# CONTROL-PANEL.net
KiCad netlist of a schematic drawn in Altium Designer
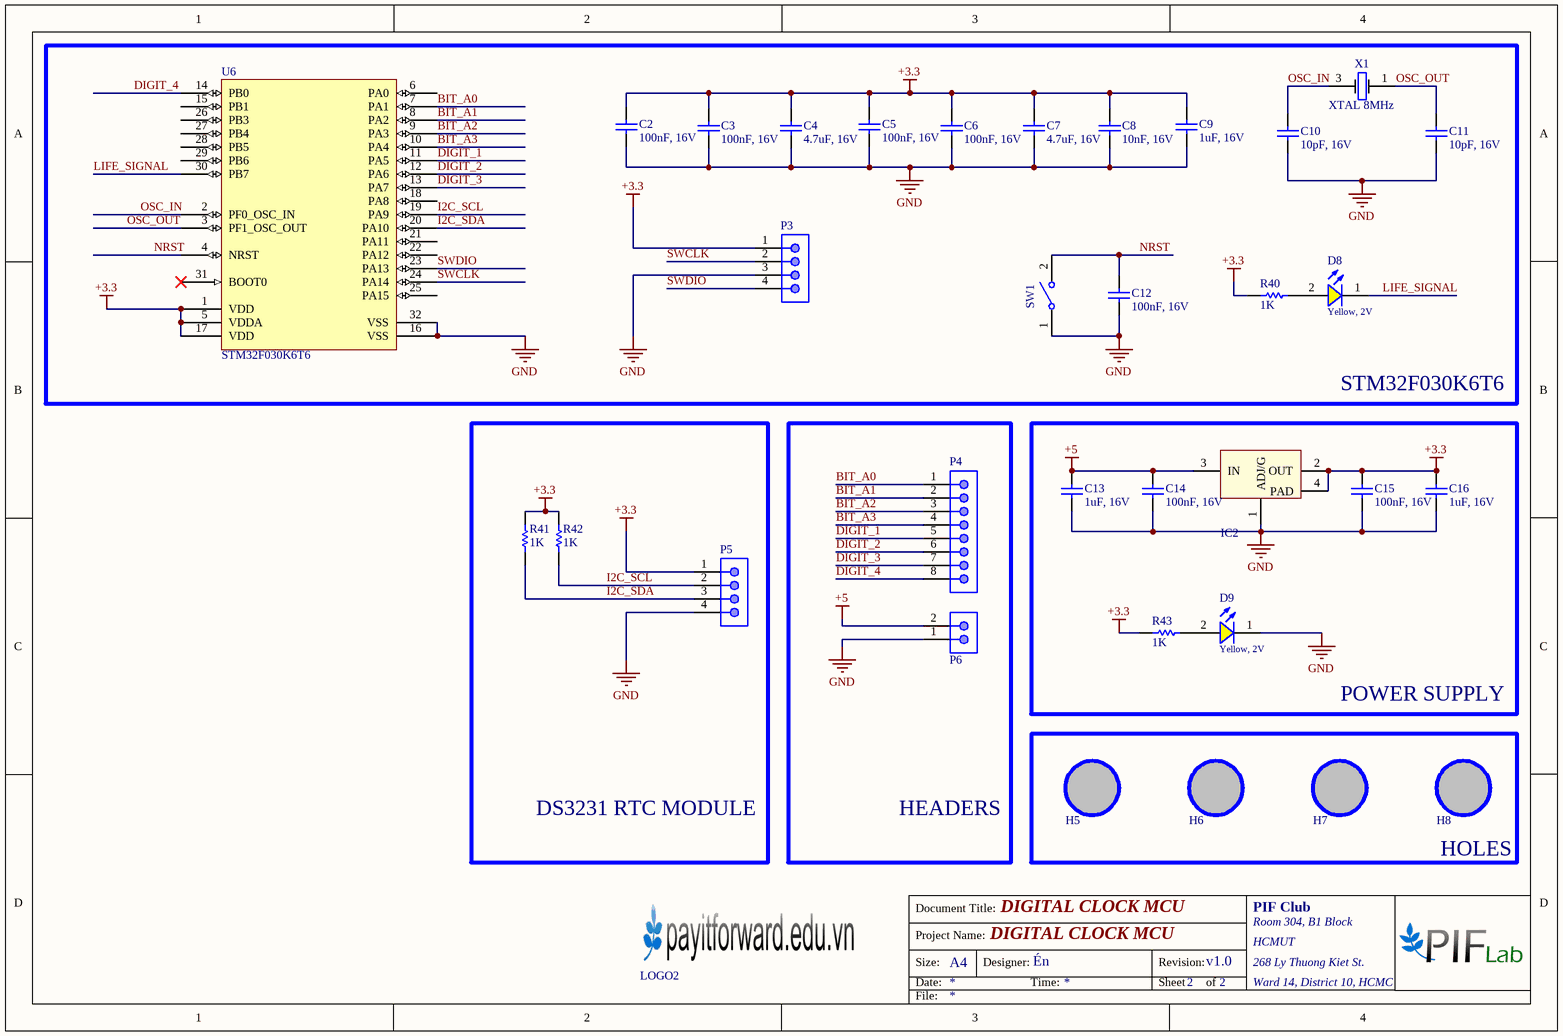
[diagram p0: CONTROL-PANEL.SchDoc]

(export (version "E")
  (design (tool "Eeschema 10.0.6"))
  (components
    (comp (ref "C2")
      (value "100nF, 16V")
      (footprint "CAP-SM-0603")
      (description "Capacitor")
      (fields (field (name "Comment") "Cap Non-Pol SMD"))
      (libsource (lib "PIF_Library") (part "Cap Non-Pol SMD"))
    )
    (comp (ref "C3")
      (value "100nF, 16V")
      (footprint "CAP-SM-0603")
      (description "Capacitor")
      (fields (field (name "Comment") "Cap Non-Pol SMD"))
      (libsource (lib "PIF_Library") (part "Cap Non-Pol SMD"))
    )
    (comp (ref "C4")
      (value "4.7uF, 16V")
      (footprint "CAP-SM-0603")
      (description "Capacitor")
      (fields (field (name "Comment") "Cap Non-Pol SMD"))
      (libsource (lib "PIF_Library") (part "Cap Non-Pol SMD"))
    )
    (comp (ref "C5")
      (value "100nF, 16V")
      (footprint "CAP-SM-0603")
      (description "Capacitor")
      (fields (field (name "Comment") "Cap Non-Pol SMD"))
      (libsource (lib "PIF_Library") (part "Cap Non-Pol SMD"))
    )
    (comp (ref "C6")
      (value "100nF, 16V")
      (footprint "CAP-SM-0603")
      (description "Capacitor")
      (fields (field (name "Comment") "Cap Non-Pol SMD"))
      (libsource (lib "PIF_Library") (part "Cap Non-Pol SMD"))
    )
    (comp (ref "C7")
      (value "4.7uF, 16V")
      (footprint "CAP-SM-0603")
      (description "Capacitor")
      (fields (field (name "Comment") "Cap Non-Pol SMD"))
      (libsource (lib "PIF_Library") (part "Cap Non-Pol SMD"))
    )
    (comp (ref "C8")
      (value "10nF, 16V")
      (footprint "CAP-SM-0603")
      (description "Capacitor")
      (fields (field (name "Comment") "Cap Non-Pol SMD"))
      (libsource (lib "PIF_Library") (part "Cap Non-Pol SMD"))
    )
    (comp (ref "C9")
      (value "1uF, 16V")
      (footprint "CAP-SM-0603")
      (description "Capacitor")
      (fields (field (name "Comment") "Cap Non-Pol SMD"))
      (libsource (lib "PIF_Library") (part "Cap Non-Pol SMD"))
    )
    (comp (ref "C10")
      (value "10pF, 16V")
      (footprint "CAP-SM-0603")
      (description "Capacitor")
      (fields (field (name "Comment") "Cap Non-Pol SMD"))
      (libsource (lib "PIF_Library") (part "Cap Non-Pol SMD"))
    )
    (comp (ref "C11")
      (value "10pF, 16V")
      (footprint "CAP-SM-0603")
      (description "Capacitor")
      (fields (field (name "Comment") "Cap Non-Pol SMD"))
      (libsource (lib "PIF_Library") (part "Cap Non-Pol SMD"))
    )
    (comp (ref "C12")
      (value "100nF, 16V")
      (footprint "CAP-SM-0603")
      (description "Capacitor")
      (fields (field (name "Comment") "Cap Non-Pol SMD"))
      (libsource (lib "PIF_Library") (part "Cap Non-Pol SMD"))
    )
    (comp (ref "C13")
      (value "1uF, 16V")
      (footprint "CAP-SM-0603")
      (description "Capacitor")
      (fields (field (name "Comment") "Cap Non-Pol SMD"))
      (libsource (lib "PIF_Library") (part "Cap Non-Pol SMD"))
    )
    (comp (ref "C14")
      (value "100nF, 16V")
      (footprint "CAP-SM-0603")
      (description "Capacitor")
      (fields (field (name "Comment") "Cap Non-Pol SMD"))
      (libsource (lib "PIF_Library") (part "Cap Non-Pol SMD"))
    )
    (comp (ref "C15")
      (value "100nF, 16V")
      (footprint "CAP-SM-0603")
      (description "Capacitor")
      (fields (field (name "Comment") "Cap Non-Pol SMD"))
      (libsource (lib "PIF_Library") (part "Cap Non-Pol SMD"))
    )
    (comp (ref "C16")
      (value "1uF, 16V")
      (footprint "CAP-SM-0603")
      (description "Capacitor")
      (fields (field (name "Comment") "Cap Non-Pol SMD"))
      (libsource (lib "PIF_Library") (part "Cap Non-Pol SMD"))
    )
    (comp (ref "D8")
      (value "Yellow, 2V")
      (footprint "WL-SMCW_0603_H=0.7mm")
      (description "WL-SMCW SMT Mono-color Chip LED Waterclear, size 0603, Yellow, 2V, 140deg")
      (fields (field (name "PART NUMBER") "150060YS75000") (field (name "PUBLISHER") "Wurth Elektronik"))
      (libsource (lib "Altium_WL-SMCW (rev20a)") (part "150060YS75000"))
    )
    (comp (ref "D9")
      (value "Yellow, 2V")
      (footprint "WL-SMCW_0603_H=0.7mm")
      (description "WL-SMCW SMT Mono-color Chip LED Waterclear, size 0603, Yellow, 2V, 140deg")
      (fields (field (name "PART NUMBER") "150060YS75000") (field (name "PUBLISHER") "Wurth Elektronik"))
      (libsource (lib "Altium_WL-SMCW (rev20a)") (part "150060YS75000"))
    )
    (comp (ref "H5")
      (value "Hole")
      (footprint "LO KHOAN 3MM")
      (description "Hole 3mm")
      (libsource (lib "PIF_Library") (part "Hole"))
    )
    (comp (ref "H6")
      (value "Hole")
      (footprint "LO KHOAN 3MM")
      (description "Hole 3mm")
      (libsource (lib "PIF_Library") (part "Hole"))
    )
    (comp (ref "H7")
      (value "Hole")
      (footprint "LO KHOAN 3MM")
      (description "Hole 3mm")
      (libsource (lib "PIF_Library") (part "Hole"))
    )
    (comp (ref "H8")
      (value "Hole")
      (footprint "LO KHOAN 3MM")
      (description "Hole 3mm")
      (libsource (lib "PIF_Library") (part "Hole"))
    )
    (comp (ref "IC2")
      (value "LM1117")
      (footprint "SOT223-4N")
      (description "Available in 1.8V, 2.5V, 2.85V, 3.3V, 5V, and  Adjustable Versions")
      (libsource (lib "PIF_Library") (part "LM1117"))
    )
    (comp (ref "LOGO2")
      (value "LOGO PIF")
      (footprint "PIF LOGO SMALL SSTOP")
      (libsource (lib "PIF_Library") (part "LOGO PIF"))
    )
    (comp (ref "P3")
      (value "61900411121")
      (footprint "61900411121")
      (description "WR-WTB THT Male Vertical Locking Header, pitch 2.54mm, 4p")
      (fields (field (name "PUBLISHER") "Wurth Elektronik"))
      (libsource (lib "653008114822_Altium_WR-WTB_rev20a") (part "61900411121"))
    )
    (comp (ref "P4")
      (value "62000811622")
      (footprint "62000811622")
      (description "WR-WTB Male Vertical Shrouded Header, pitch 2mm, 8p")
      (fields (field (name "PUBLISHER") "Wurth Elektronik"))
      (libsource (lib "653008114822_Altium_WR-WTB_rev20a") (part "62000811622"))
    )
    (comp (ref "P5")
      (value "62000411622")
      (footprint "62000411622")
      (description "WR-WTB Male Vertical Shrouded Header, pitch 2mm, 4p")
      (fields (field (name "PUBLISHER") "Wurth Elektronik"))
      (libsource (lib "653008114822_Altium_WR-WTB_rev20a") (part "62000411622"))
    )
    (comp (ref "P6")
      (value "62000211622")
      (footprint "62000211622")
      (description "WR-WTB Male Vertical Shrouded Header, pitch 2mm, 2p")
      (fields (field (name "PUBLISHER") "Wurth Elektronik"))
      (libsource (lib "653008114822_Altium_WR-WTB_rev20a") (part "62000211622"))
    )
    (comp (ref "R40")
      (value "1K")
      (footprint "RES-SM-0603")
      (description "Resistor")
      (fields (field (name "Comment") "RESISTOR SMD"))
      (libsource (lib "PIF_Library") (part "RESISTOR SMD"))
    )
    (comp (ref "R41")
      (value "1K")
      (footprint "RES-SM-0603")
      (description "Resistor")
      (fields (field (name "Comment") "RESISTOR SMD"))
      (libsource (lib "PIF_Library") (part "RESISTOR SMD"))
    )
    (comp (ref "R42")
      (value "1K")
      (footprint "RES-SM-0603")
      (description "Resistor")
      (fields (field (name "Comment") "RESISTOR SMD"))
      (libsource (lib "PIF_Library") (part "RESISTOR SMD"))
    )
    (comp (ref "R43")
      (value "1K")
      (footprint "RES-SM-0603")
      (description "Resistor")
      (fields (field (name "Comment") "RESISTOR SMD"))
      (libsource (lib "PIF_Library") (part "RESISTOR SMD"))
    )
    (comp (ref "SW1")
      (value "434111025826")
      (footprint "WS-TASV_L6W3.8H2.5_4341x10258x6")
      (description "WS-TASV SMT Tact Switch, 12VDC, 50mA, 260g, height 2.5mm")
      (fields (field (name "MANUFACTURER") "Wurth Elektronik"))
      (libsource (lib "Altium_WS-TASV (rev22a)") (part "434111025826"))
    )
    (comp (ref "U6")
      (value "STM32F030K6T6")
      (footprint "STM32F030K6T6")
      (description "ARM Cortex M0 Microcontroller IC 32-Bit 48MHz 32KB FLASH, 32-LQFP")
      (fields (field (name "MFR") "STMicroelectronics"))
      (libsource (lib "Giang's Libs") (part "STM32F030K6T6"))
    )
    (comp (ref "X1") (value "XTAL 8MHz") (footprint "XTAL 3225") (libsource (lib "MiclsLib") (part "XTAL")))
  )
  (nets
    (net (code "1") (name "+3.3") (class "Default")
      (node (ref "C15") (pin "2") (pinfunction "2_2") (pintype "passive"))
      (node (ref "C16") (pin "2") (pinfunction "2_2") (pintype "passive"))
      (node (ref "C2") (pin "2") (pinfunction "2_2") (pintype "passive"))
      (node (ref "C3") (pin "2") (pinfunction "2_2") (pintype "passive"))
      (node (ref "C4") (pin "2") (pinfunction "2_2") (pintype "passive"))
      (node (ref "C5") (pin "2") (pinfunction "2_2") (pintype "passive"))
      (node (ref "C6") (pin "2") (pinfunction "2_2") (pintype "passive"))
      (node (ref "C7") (pin "2") (pinfunction "2_2") (pintype "passive"))
      (node (ref "C8") (pin "2") (pinfunction "2_2") (pintype "passive"))
      (node (ref "C9") (pin "2") (pinfunction "2_2") (pintype "passive"))
      (node (ref "IC2") (pin "2") (pinfunction "OUT_2") (pintype "passive"))
      (node (ref "IC2") (pin "4") (pinfunction "PAD_4") (pintype "passive"))
      (node (ref "P3") (pin "1") (pinfunction "1_1") (pintype "passive"))
      (node (ref "P5") (pin "1") (pinfunction "1_1") (pintype "passive"))
      (node (ref "R40") (pin "2") (pinfunction "2_2") (pintype "passive"))
      (node (ref "R41") (pin "1") (pinfunction "1_1") (pintype "passive"))
      (node (ref "R42") (pin "1") (pinfunction "1_1") (pintype "passive"))
      (node (ref "R43") (pin "2") (pinfunction "2_2") (pintype "passive"))
      (node (ref "U6") (pin "1") (pinfunction "VDD_1") (pintype "power_in"))
      (node (ref "U6") (pin "17") (pinfunction "VDD_17") (pintype "power_in"))
      (node (ref "U6") (pin "5") (pinfunction "VDDA_5") (pintype "power_in"))
    )
    (net (code "2") (name "+5") (class "Default")
      (node (ref "C13") (pin "2") (pinfunction "2_2") (pintype "passive"))
      (node (ref "C14") (pin "2") (pinfunction "2_2") (pintype "passive"))
      (node (ref "IC2") (pin "3") (pinfunction "IN_3") (pintype "passive"))
      (node (ref "P6") (pin "2") (pinfunction "2_2") (pintype "passive"))
    )
    (net (code "3") (name "/BIT_A0") (class "Default")
      (node (ref "P4") (pin "1") (pinfunction "1_1") (pintype "passive"))
      (node (ref "U6") (pin "7") (pinfunction "PA1_7") (pintype "bidirectional"))
    )
    (net (code "4") (name "/BIT_A1") (class "Default")
      (node (ref "P4") (pin "2") (pinfunction "2_2") (pintype "passive"))
      (node (ref "U6") (pin "8") (pinfunction "PA2_8") (pintype "bidirectional"))
    )
    (net (code "5") (name "/BIT_A2") (class "Default")
      (node (ref "P4") (pin "3") (pinfunction "3_3") (pintype "passive"))
      (node (ref "U6") (pin "9") (pinfunction "PA3_9") (pintype "bidirectional"))
    )
    (net (code "6") (name "/BIT_A3") (class "Default")
      (node (ref "P4") (pin "4") (pinfunction "4_4") (pintype "passive"))
      (node (ref "U6") (pin "10") (pinfunction "PA4_10") (pintype "bidirectional"))
    )
    (net (code "7") (name "/DIGIT_1") (class "Default")
      (node (ref "P4") (pin "5") (pinfunction "5_5") (pintype "passive"))
      (node (ref "U6") (pin "11") (pinfunction "PA5_11") (pintype "bidirectional"))
    )
    (net (code "8") (name "/DIGIT_2") (class "Default")
      (node (ref "P4") (pin "6") (pinfunction "6_6") (pintype "passive"))
      (node (ref "U6") (pin "12") (pinfunction "PA6_12") (pintype "bidirectional"))
    )
    (net (code "9") (name "/DIGIT_3") (class "Default")
      (node (ref "P4") (pin "7") (pinfunction "7_7") (pintype "passive"))
      (node (ref "U6") (pin "13") (pinfunction "PA7_13") (pintype "bidirectional"))
    )
    (net (code "10") (name "/DIGIT_4") (class "Default")
      (node (ref "P4") (pin "8") (pinfunction "8_8") (pintype "passive"))
      (node (ref "U6") (pin "14") (pinfunction "PB0_14") (pintype "bidirectional"))
    )
    (net (code "11") (name "/I2C_SCL") (class "Default")
      (node (ref "P5") (pin "2") (pinfunction "2_2") (pintype "passive"))
      (node (ref "R42") (pin "2") (pinfunction "2_2") (pintype "passive"))
      (node (ref "U6") (pin "19") (pinfunction "PA9_19") (pintype "bidirectional"))
    )
    (net (code "12") (name "/I2C_SDA") (class "Default")
      (node (ref "P5") (pin "3") (pinfunction "3_3") (pintype "passive"))
      (node (ref "R41") (pin "2") (pinfunction "2_2") (pintype "passive"))
      (node (ref "U6") (pin "20") (pinfunction "PA10_20") (pintype "bidirectional"))
    )
    (net (code "13") (name "/LIFE_SIGNAL") (class "Default")
      (node (ref "D8") (pin "1") (pinfunction "K_1") (pintype "passive"))
      (node (ref "U6") (pin "30") (pinfunction "PB7_30") (pintype "bidirectional"))
    )
    (net (code "14") (name "/NRST") (class "Default")
      (node (ref "C12") (pin "2") (pinfunction "2_2") (pintype "passive"))
      (node (ref "SW1") (pin "2") (pinfunction "2_2") (pintype "passive"))
      (node (ref "U6") (pin "4") (pinfunction "NRST_4") (pintype "bidirectional"))
    )
    (net (code "15") (name "/OSC_IN") (class "Default")
      (node (ref "C10") (pin "2") (pinfunction "2_2") (pintype "passive"))
      (node (ref "U6") (pin "2") (pinfunction "PF0_OSC_IN_2") (pintype "bidirectional"))
      (node (ref "X1") (pin "3") (pinfunction "9_3") (pintype "passive"))
    )
    (net (code "16") (name "/OSC_OUT") (class "Default")
      (node (ref "C11") (pin "2") (pinfunction "2_2") (pintype "passive"))
      (node (ref "U6") (pin "3") (pinfunction "PF1_OSC_OUT_3") (pintype "bidirectional"))
      (node (ref "X1") (pin "1") (pinfunction "8_1") (pintype "passive"))
    )
    (net (code "17") (name "/SWCLK") (class "Default")
      (node (ref "P3") (pin "2") (pinfunction "2_2") (pintype "passive"))
      (node (ref "U6") (pin "24") (pinfunction "PA14_24") (pintype "bidirectional"))
    )
    (net (code "18") (name "/SWDIO") (class "Default")
      (node (ref "P3") (pin "4") (pinfunction "4_4") (pintype "passive"))
      (node (ref "U6") (pin "23") (pinfunction "PA13_23") (pintype "bidirectional"))
    )
    (net (code "19") (name "GND") (class "Default")
      (node (ref "C10") (pin "1") (pinfunction "1_1") (pintype "passive"))
      (node (ref "C11") (pin "1") (pinfunction "1_1") (pintype "passive"))
      (node (ref "C12") (pin "1") (pinfunction "1_1") (pintype "passive"))
      (node (ref "C13") (pin "1") (pinfunction "1_1") (pintype "passive"))
      (node (ref "C14") (pin "1") (pinfunction "1_1") (pintype "passive"))
      (node (ref "C15") (pin "1") (pinfunction "1_1") (pintype "passive"))
      (node (ref "C16") (pin "1") (pinfunction "1_1") (pintype "passive"))
      (node (ref "C2") (pin "1") (pinfunction "1_1") (pintype "passive"))
      (node (ref "C3") (pin "1") (pinfunction "1_1") (pintype "passive"))
      (node (ref "C4") (pin "1") (pinfunction "1_1") (pintype "passive"))
      (node (ref "C5") (pin "1") (pinfunction "1_1") (pintype "passive"))
      (node (ref "C6") (pin "1") (pinfunction "1_1") (pintype "passive"))
      (node (ref "C7") (pin "1") (pinfunction "1_1") (pintype "passive"))
      (node (ref "C8") (pin "1") (pinfunction "1_1") (pintype "passive"))
      (node (ref "C9") (pin "1") (pinfunction "1_1") (pintype "passive"))
      (node (ref "D9") (pin "1") (pinfunction "K_1") (pintype "passive"))
      (node (ref "IC2") (pin "1") (pinfunction "ADJ/G_1") (pintype "passive"))
      (node (ref "P3") (pin "3") (pinfunction "3_3") (pintype "passive"))
      (node (ref "P5") (pin "4") (pinfunction "4_4") (pintype "passive"))
      (node (ref "P6") (pin "1") (pinfunction "1_1") (pintype "passive"))
      (node (ref "SW1") (pin "1") (pinfunction "1_1") (pintype "passive"))
      (node (ref "U6") (pin "16") (pinfunction "VSS_16") (pintype "power_in"))
      (node (ref "U6") (pin "32") (pinfunction "VSS_32") (pintype "power_in"))
    )
    (net (code "20") (name "Net-(D8-A)") (class "Default")
      (node (ref "D8") (pin "2") (pinfunction "A_2") (pintype "passive"))
      (node (ref "R40") (pin "1") (pinfunction "1_1") (pintype "passive"))
    )
    (net (code "21") (name "Net-(D9-A)") (class "Default")
      (node (ref "D9") (pin "2") (pinfunction "A_2") (pintype "passive"))
      (node (ref "R43") (pin "1") (pinfunction "1_1") (pintype "passive"))
    )
    (net (code "22") (name "unconnected-(H5-Pad1)") (class "Default")
      (node (ref "H5") (pin "1") (pinfunction "1_1") (pintype "passive"))
    )
    (net (code "23") (name "unconnected-(H6-Pad1)") (class "Default")
      (node (ref "H6") (pin "1") (pinfunction "1_1") (pintype "passive"))
    )
    (net (code "24") (name "unconnected-(H7-Pad1)") (class "Default")
      (node (ref "H7") (pin "1") (pinfunction "1_1") (pintype "passive"))
    )
    (net (code "25") (name "unconnected-(H8-Pad1)") (class "Default")
      (node (ref "H8") (pin "1") (pinfunction "1_1") (pintype "passive"))
    )
    (net (code "26") (name "unconnected-(U6-BOOT0-Pad31)") (class "Default")
      (node (ref "U6") (pin "31") (pinfunction "BOOT0_31") (pintype "input+no_connect"))
    )
    (net (code "27") (name "unconnected-(U6-PA0-Pad6)") (class "Default")
      (node (ref "U6") (pin "6") (pinfunction "PA0_6") (pintype "bidirectional"))
    )
    (net (code "28") (name "unconnected-(U6-PA8-Pad18)") (class "Default")
      (node (ref "U6") (pin "18") (pinfunction "PA8_18") (pintype "bidirectional"))
    )
    (net (code "29") (name "unconnected-(U6-PA11-Pad21)") (class "Default")
      (node (ref "U6") (pin "21") (pinfunction "PA11_21") (pintype "bidirectional"))
    )
    (net (code "30") (name "unconnected-(U6-PA12-Pad22)") (class "Default")
      (node (ref "U6") (pin "22") (pinfunction "PA12_22") (pintype "bidirectional"))
    )
    (net (code "31") (name "unconnected-(U6-PA15-Pad25)") (class "Default")
      (node (ref "U6") (pin "25") (pinfunction "PA15_25") (pintype "bidirectional"))
    )
    (net (code "32") (name "unconnected-(U6-PB1-Pad15)") (class "Default")
      (node (ref "U6") (pin "15") (pinfunction "PB1_15") (pintype "bidirectional"))
    )
    (net (code "33") (name "unconnected-(U6-PB3-Pad26)") (class "Default")
      (node (ref "U6") (pin "26") (pinfunction "PB3_26") (pintype "bidirectional"))
    )
    (net (code "34") (name "unconnected-(U6-PB4-Pad27)") (class "Default")
      (node (ref "U6") (pin "27") (pinfunction "PB4_27") (pintype "bidirectional"))
    )
    (net (code "35") (name "unconnected-(U6-PB5-Pad28)") (class "Default")
      (node (ref "U6") (pin "28") (pinfunction "PB5_28") (pintype "bidirectional"))
    )
    (net (code "36") (name "unconnected-(U6-PB6-Pad29)") (class "Default")
      (node (ref "U6") (pin "29") (pinfunction "PB6_29") (pintype "bidirectional"))
    )
  )
)
